# Sheet2.net
KiCad netlist of a schematic drawn in Altium Designer
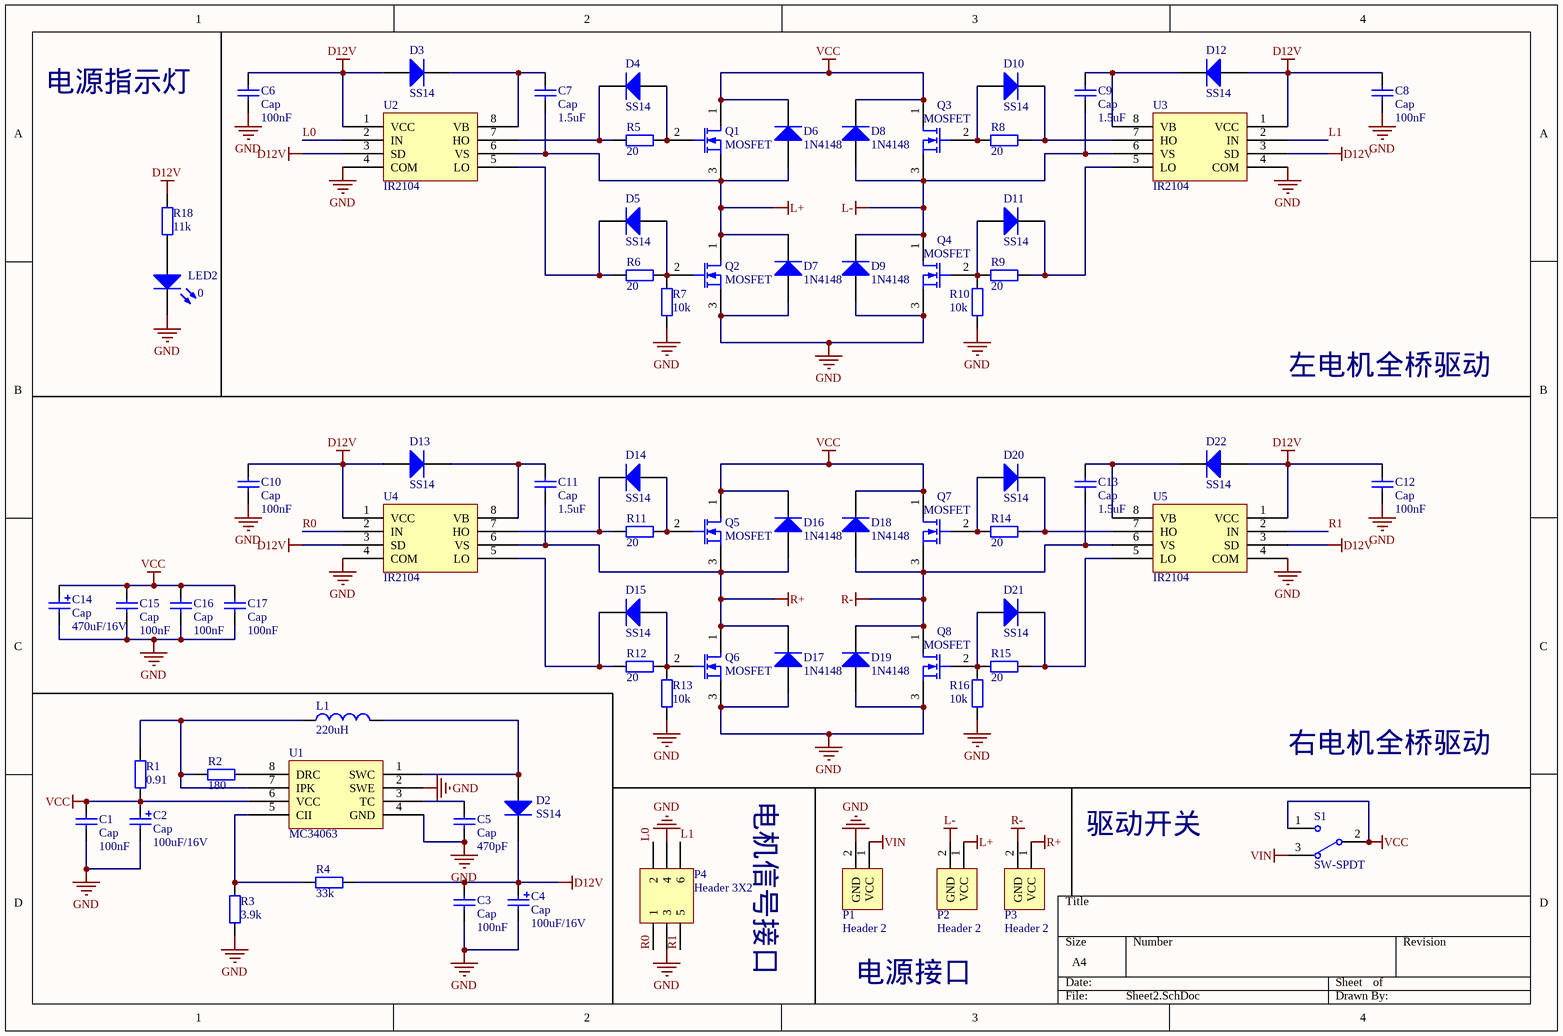
[diagram p0: Sheet2.SchDoc]

(export (version "E")
  (design (tool "Eeschema 10.0.6"))
  (components
    (comp (ref "C1")
      (value "Cap")
      (footprint "0603C")
      (description "Capacitor")
      (fields (field (name "ALTIUM_VALUE") "100nF") (field (name "PUBLISHER") "Altium Limited"))
      (libsource (lib "Schlib1") (part "Cap"))
    )
    (comp (ref "C2")
      (value "Cap")
      (footprint "电解电容")
      (description "Capacitor")
      (fields (field (name "ALTIUM_VALUE") "100uF/16V") (field (name "PUBLISHER") "Altium Limited"))
      (libsource (lib "Schlib1") (part "Cap2"))
    )
    (comp (ref "C3")
      (value "Cap")
      (footprint "0603C")
      (description "Capacitor")
      (fields (field (name "ALTIUM_VALUE") "100nF") (field (name "PUBLISHER") "Altium Limited"))
      (libsource (lib "Schlib1") (part "Cap"))
    )
    (comp (ref "C4")
      (value "Cap")
      (footprint "电解电容")
      (description "Capacitor")
      (fields (field (name "ALTIUM_VALUE") "100uF/16V") (field (name "PUBLISHER") "Altium Limited"))
      (libsource (lib "Schlib1") (part "Cap2"))
    )
    (comp (ref "C5")
      (value "Cap")
      (footprint "0603C")
      (description "Capacitor")
      (fields (field (name "ALTIUM_VALUE") "470pF") (field (name "PUBLISHER") "Altium Limited"))
      (libsource (lib "Schlib1") (part "Cap"))
    )
    (comp (ref "C6")
      (value "Cap")
      (footprint "0603C")
      (description "Capacitor")
      (fields (field (name "ALTIUM_VALUE") "100nF") (field (name "PUBLISHER") "Altium Limited"))
      (libsource (lib "Schlib1") (part "Cap"))
    )
    (comp (ref "C7")
      (value "Cap")
      (footprint "0603C")
      (description "Capacitor")
      (fields (field (name "ALTIUM_VALUE") "1.5uF") (field (name "PUBLISHER") "Altium Limited"))
      (libsource (lib "Schlib1") (part "Cap"))
    )
    (comp (ref "C8")
      (value "Cap")
      (footprint "0603C")
      (description "Capacitor")
      (fields (field (name "ALTIUM_VALUE") "100nF") (field (name "PUBLISHER") "Altium Limited"))
      (libsource (lib "Schlib1") (part "Cap"))
    )
    (comp (ref "C9")
      (value "Cap")
      (footprint "0603C")
      (description "Capacitor")
      (fields (field (name "ALTIUM_VALUE") "1.5uF") (field (name "PUBLISHER") "Altium Limited"))
      (libsource (lib "Schlib1") (part "Cap"))
    )
    (comp (ref "C10")
      (value "Cap")
      (footprint "0603C")
      (description "Capacitor")
      (fields (field (name "ALTIUM_VALUE") "100nF") (field (name "PUBLISHER") "Altium Limited"))
      (libsource (lib "Schlib1") (part "Cap"))
    )
    (comp (ref "C11")
      (value "Cap")
      (footprint "0603C")
      (description "Capacitor")
      (fields (field (name "ALTIUM_VALUE") "1.5uF") (field (name "PUBLISHER") "Altium Limited"))
      (libsource (lib "Schlib1") (part "Cap"))
    )
    (comp (ref "C12")
      (value "Cap")
      (footprint "0603C")
      (description "Capacitor")
      (fields (field (name "ALTIUM_VALUE") "100nF") (field (name "PUBLISHER") "Altium Limited"))
      (libsource (lib "Schlib1") (part "Cap"))
    )
    (comp (ref "C13")
      (value "Cap")
      (footprint "0603C")
      (description "Capacitor")
      (fields (field (name "ALTIUM_VALUE") "1.5uF") (field (name "PUBLISHER") "Altium Limited"))
      (libsource (lib "Schlib1") (part "Cap"))
    )
    (comp (ref "C14")
      (value "Cap")
      (footprint "CAP5.08/8")
      (description "Capacitor")
      (fields (field (name "ALTIUM_VALUE") "470uF/16V") (field (name "PUBLISHER") "Altium Limited"))
      (libsource (lib "Schlib1") (part "Cap2"))
    )
    (comp (ref "C15")
      (value "Cap")
      (footprint "0603C")
      (description "Capacitor")
      (fields (field (name "ALTIUM_VALUE") "100nF") (field (name "PUBLISHER") "Altium Limited"))
      (libsource (lib "Schlib1") (part "Cap"))
    )
    (comp (ref "C16")
      (value "Cap")
      (footprint "0603C")
      (description "Capacitor")
      (fields (field (name "ALTIUM_VALUE") "100nF") (field (name "PUBLISHER") "Altium Limited"))
      (libsource (lib "Schlib1") (part "Cap"))
    )
    (comp (ref "C17")
      (value "Cap")
      (footprint "0603C")
      (description "Capacitor")
      (fields (field (name "ALTIUM_VALUE") "100nF") (field (name "PUBLISHER") "Altium Limited"))
      (libsource (lib "Schlib1") (part "Cap"))
    )
    (comp (ref "D2")
      (value "SS14")
      (footprint "ss54")
      (description "Default Diode")
      (fields (field (name "PUBLISHER") "Altium Limited"))
      (libsource (lib "Schlib1") (part "Diode_1"))
    )
    (comp (ref "D3")
      (value "SS14")
      (footprint "ss54")
      (description "Default Diode")
      (fields (field (name "PUBLISHER") "Altium Limited"))
      (libsource (lib "Schlib1") (part "Diode_1"))
    )
    (comp (ref "D4")
      (value "SS14")
      (footprint "ss54")
      (description "Default Diode")
      (fields (field (name "PUBLISHER") "Altium Limited"))
      (libsource (lib "Schlib1") (part "Diode_1"))
    )
    (comp (ref "D5")
      (value "SS14")
      (footprint "ss54")
      (description "Default Diode")
      (fields (field (name "PUBLISHER") "Altium Limited"))
      (libsource (lib "Schlib1") (part "Diode_1"))
    )
    (comp (ref "D6")
      (value "1N4148")
      (footprint "SOD123")
      (description "Default Diode")
      (fields (field (name "PUBLISHER") "Altium Limited"))
      (libsource (lib "Schlib1") (part "Diode_2"))
    )
    (comp (ref "D7")
      (value "1N4148")
      (footprint "SOD123")
      (description "Default Diode")
      (fields (field (name "PUBLISHER") "Altium Limited"))
      (libsource (lib "Schlib1") (part "Diode_2"))
    )
    (comp (ref "D8")
      (value "1N4148")
      (footprint "SOD123")
      (description "Default Diode")
      (fields (field (name "PUBLISHER") "Altium Limited"))
      (libsource (lib "Schlib1") (part "Diode_2"))
    )
    (comp (ref "D9")
      (value "1N4148")
      (footprint "SOD123")
      (description "Default Diode")
      (fields (field (name "PUBLISHER") "Altium Limited"))
      (libsource (lib "Schlib1") (part "Diode_2"))
    )
    (comp (ref "D10")
      (value "SS14")
      (footprint "ss54")
      (description "Default Diode")
      (fields (field (name "PUBLISHER") "Altium Limited"))
      (libsource (lib "Schlib1") (part "Diode_1"))
    )
    (comp (ref "D11")
      (value "SS14")
      (footprint "ss54")
      (description "Default Diode")
      (fields (field (name "PUBLISHER") "Altium Limited"))
      (libsource (lib "Schlib1") (part "Diode_1"))
    )
    (comp (ref "D12")
      (value "SS14")
      (footprint "ss54")
      (description "Default Diode")
      (fields (field (name "PUBLISHER") "Altium Limited"))
      (libsource (lib "Schlib1") (part "Diode_1"))
    )
    (comp (ref "D13")
      (value "SS14")
      (footprint "ss54")
      (description "Default Diode")
      (fields (field (name "PUBLISHER") "Altium Limited"))
      (libsource (lib "Schlib1") (part "Diode_1"))
    )
    (comp (ref "D14")
      (value "SS14")
      (footprint "ss54")
      (description "Default Diode")
      (fields (field (name "PUBLISHER") "Altium Limited"))
      (libsource (lib "Schlib1") (part "Diode_1"))
    )
    (comp (ref "D15")
      (value "SS14")
      (footprint "ss54")
      (description "Default Diode")
      (fields (field (name "PUBLISHER") "Altium Limited"))
      (libsource (lib "Schlib1") (part "Diode_1"))
    )
    (comp (ref "D16")
      (value "1N4148")
      (footprint "SOD123")
      (description "Default Diode")
      (fields (field (name "PUBLISHER") "Altium Limited"))
      (libsource (lib "Schlib1") (part "Diode_2"))
    )
    (comp (ref "D17")
      (value "1N4148")
      (footprint "SOD123")
      (description "Default Diode")
      (fields (field (name "PUBLISHER") "Altium Limited"))
      (libsource (lib "Schlib1") (part "Diode_2"))
    )
    (comp (ref "D18")
      (value "1N4148")
      (footprint "SOD123")
      (description "Default Diode")
      (fields (field (name "PUBLISHER") "Altium Limited"))
      (libsource (lib "Schlib1") (part "Diode_2"))
    )
    (comp (ref "D19")
      (value "1N4148")
      (footprint "SOD123")
      (description "Default Diode")
      (fields (field (name "PUBLISHER") "Altium Limited"))
      (libsource (lib "Schlib1") (part "Diode_2"))
    )
    (comp (ref "D20")
      (value "SS14")
      (footprint "ss54")
      (description "Default Diode")
      (fields (field (name "PUBLISHER") "Altium Limited"))
      (libsource (lib "Schlib1") (part "Diode_1"))
    )
    (comp (ref "D21")
      (value "SS14")
      (footprint "ss54")
      (description "Default Diode")
      (fields (field (name "PUBLISHER") "Altium Limited"))
      (libsource (lib "Schlib1") (part "Diode_1"))
    )
    (comp (ref "D22")
      (value "SS14")
      (footprint "ss54")
      (description "Default Diode")
      (fields (field (name "PUBLISHER") "Altium Limited"))
      (libsource (lib "Schlib1") (part "Diode_1"))
    )
    (comp (ref "L1")
      (value "220uH")
      (footprint "cd54")
      (description "Inductor")
      (fields (field (name "PUBLISHER") "Altium Limited"))
      (libsource (lib "Schlib1") (part "Inductor_2"))
    )
    (comp (ref "LED2")
      (value "0")
      (footprint "0603C")
      (description "Typical RED, GREEN, YELLOW, AMBER GaAs LED")
      (fields (field (name "PUBLISHER") "Altium Limited"))
      (libsource (lib "Schlib1") (part "LED2"))
    )
    (comp (ref "P1")
      (value "Header 2")
      (footprint "VCCBAT")
      (description "Header, 2-Pin")
      (fields (field (name "PUBLISHER") "Altium Limited"))
      (libsource (lib "Schlib1") (part "Header 2_2"))
    )
    (comp (ref "P2")
      (value "Header 2")
      (footprint "VCCBAT")
      (description "Header, 2-Pin")
      (fields (field (name "PUBLISHER") "Altium Limited"))
      (libsource (lib "Schlib1") (part "Header 2_2"))
    )
    (comp (ref "P3")
      (value "Header 2")
      (footprint "VCCBAT")
      (description "Header, 2-Pin")
      (fields (field (name "PUBLISHER") "Altium Limited"))
      (libsource (lib "Schlib1") (part "Header 2_2"))
    )
    (comp (ref "P4")
      (value "Header 3X2")
      (footprint "HDR2X3")
      (description "Header, 3-Pin, Dual row")
      (fields (field (name "PUBLISHER") "Altium Limited"))
      (libsource (lib "Miscellaneous Connectors") (part "Header 3X2"))
    )
    (comp (ref "Q1") (value "MOSFET") (footprint "DPAK-1") (libsource (lib "Schlib1") (part "MOSFET-N")))
    (comp (ref "Q2") (value "MOSFET") (footprint "DPAK-1") (libsource (lib "Schlib1") (part "MOSFET-N")))
    (comp (ref "Q3") (value "MOSFET") (footprint "DPAK-1") (libsource (lib "Schlib1") (part "MOSFET-N")))
    (comp (ref "Q4") (value "MOSFET") (footprint "DPAK-1") (libsource (lib "Schlib1") (part "MOSFET-N")))
    (comp (ref "Q5") (value "MOSFET") (footprint "DPAK-1") (libsource (lib "Schlib1") (part "MOSFET-N")))
    (comp (ref "Q6") (value "MOSFET") (footprint "DPAK-1") (libsource (lib "Schlib1") (part "MOSFET-N")))
    (comp (ref "Q7") (value "MOSFET") (footprint "DPAK-1") (libsource (lib "Schlib1") (part "MOSFET-N")))
    (comp (ref "Q8") (value "MOSFET") (footprint "DPAK-1") (libsource (lib "Schlib1") (part "MOSFET-N")))
    (comp (ref "R1")
      (value "0.91")
      (footprint "0603R")
      (description "Resistor")
      (fields (field (name "Comment") "Res2") (field (name "PUBLISHER") "Altium Limited"))
      (libsource (lib "Schlib1") (part "Res2"))
    )
    (comp (ref "R2")
      (value "180")
      (footprint "0603R")
      (description "Resistor")
      (fields (field (name "Comment") "Res2") (field (name "PUBLISHER") "Altium Limited"))
      (libsource (lib "") (part "Res2_1"))
    )
    (comp (ref "R3")
      (value "3.9k")
      (footprint "0603R")
      (description "Resistor")
      (fields (field (name "Comment") "Res2") (field (name "PUBLISHER") "Altium Limited"))
      (libsource (lib "") (part "Res2_2"))
    )
    (comp (ref "R4")
      (value "33k")
      (footprint "0603R")
      (description "Resistor")
      (fields (field (name "Comment") "Res2") (field (name "PUBLISHER") "Altium Limited"))
      (libsource (lib "") (part "Res2_1"))
    )
    (comp (ref "R5")
      (value "20")
      (footprint "0603R")
      (description "Resistor")
      (fields (field (name "Comment") "Res2") (field (name "PUBLISHER") "Altium Limited"))
      (libsource (lib "") (part "Res2_1"))
    )
    (comp (ref "R6")
      (value "20")
      (footprint "0603R")
      (description "Resistor")
      (fields (field (name "Comment") "Res2") (field (name "PUBLISHER") "Altium Limited"))
      (libsource (lib "") (part "Res2_1"))
    )
    (comp (ref "R7")
      (value "10k")
      (footprint "0603R")
      (description "Resistor")
      (fields (field (name "Comment") "Res2") (field (name "PUBLISHER") "Altium Limited"))
      (libsource (lib "Schlib1") (part "Res2"))
    )
    (comp (ref "R8")
      (value "20")
      (footprint "0603R")
      (description "Resistor")
      (fields (field (name "Comment") "Res2") (field (name "PUBLISHER") "Altium Limited"))
      (libsource (lib "Schlib1") (part "Res2"))
    )
    (comp (ref "R9")
      (value "20")
      (footprint "0603R")
      (description "Resistor")
      (fields (field (name "Comment") "Res2") (field (name "PUBLISHER") "Altium Limited"))
      (libsource (lib "Schlib1") (part "Res2"))
    )
    (comp (ref "R10")
      (value "10k")
      (footprint "0603R")
      (description "Resistor")
      (fields (field (name "Comment") "Res2") (field (name "PUBLISHER") "Altium Limited"))
      (libsource (lib "") (part "Res2_3"))
    )
    (comp (ref "R11")
      (value "20")
      (footprint "0603R")
      (description "Resistor")
      (fields (field (name "Comment") "Res2") (field (name "PUBLISHER") "Altium Limited"))
      (libsource (lib "") (part "Res2_1"))
    )
    (comp (ref "R12")
      (value "20")
      (footprint "0603R")
      (description "Resistor")
      (fields (field (name "Comment") "Res2") (field (name "PUBLISHER") "Altium Limited"))
      (libsource (lib "") (part "Res2_1"))
    )
    (comp (ref "R13")
      (value "10k")
      (footprint "0603R")
      (description "Resistor")
      (fields (field (name "Comment") "Res2") (field (name "PUBLISHER") "Altium Limited"))
      (libsource (lib "Schlib1") (part "Res2"))
    )
    (comp (ref "R14")
      (value "20")
      (footprint "0603R")
      (description "Resistor")
      (fields (field (name "Comment") "Res2") (field (name "PUBLISHER") "Altium Limited"))
      (libsource (lib "Schlib1") (part "Res2"))
    )
    (comp (ref "R15")
      (value "20")
      (footprint "0603R")
      (description "Resistor")
      (fields (field (name "Comment") "Res2") (field (name "PUBLISHER") "Altium Limited"))
      (libsource (lib "Schlib1") (part "Res2"))
    )
    (comp (ref "R16")
      (value "10k")
      (footprint "0603R")
      (description "Resistor")
      (fields (field (name "Comment") "Res2") (field (name "PUBLISHER") "Altium Limited"))
      (libsource (lib "") (part "Res2_3"))
    )
    (comp (ref "R18")
      (value "11k")
      (footprint "0603R")
      (description "Resistor")
      (fields (field (name "Comment") "Res2") (field (name "PUBLISHER") "Altium Limited"))
      (libsource (lib "Schlib1") (part "Res2"))
    )
    (comp (ref "S1")
      (value "SW-SPDT")
      (footprint "SW")
      (description "SPDT Subminiature Toggle Switch, Right Angle Mounting, Vertical Actuation")
      (fields (field (name "PUBLISHER") "Altium Limited"))
      (libsource (lib "Miscellaneous Devices") (part "SW-SPDT"))
    )
    (comp (ref "U1") (value "MC34063") (footprint "SOIC-8") (libsource (lib "Schlib1") (part "MC34063")))
    (comp (ref "U2") (value "IR2104") (footprint "SOIC-8") (libsource (lib "") (part "IR2104_1")))
    (comp (ref "U3") (value "IR2104") (footprint "SOIC-8") (libsource (lib "Schlib1") (part "IR2104")))
    (comp (ref "U4") (value "IR2104") (footprint "SOIC-8") (libsource (lib "") (part "IR2104_1")))
    (comp (ref "U5") (value "IR2104") (footprint "SOIC-8") (libsource (lib "Schlib1") (part "IR2104")))
  )
  (nets
    (net (code "1") (name "/L0") (class "Default")
      (node (ref "P4") (pin "2") (pinfunction "2_2") (pintype "passive"))
      (node (ref "U2") (pin "2") (pinfunction "IN_2") (pintype "passive"))
    )
    (net (code "2") (name "/L1") (class "Default")
      (node (ref "P4") (pin "6") (pinfunction "6_6") (pintype "passive"))
      (node (ref "U3") (pin "2") (pinfunction "IN_2") (pintype "passive"))
    )
    (net (code "3") (name "/R0") (class "Default")
      (node (ref "P4") (pin "1") (pinfunction "1_1") (pintype "passive"))
      (node (ref "U4") (pin "2") (pinfunction "IN_2") (pintype "passive"))
    )
    (net (code "4") (name "/R1") (class "Default")
      (node (ref "P4") (pin "5") (pinfunction "5_5") (pintype "passive"))
      (node (ref "U5") (pin "2") (pinfunction "IN_2") (pintype "passive"))
    )
    (net (code "5") (name "D12V") (class "Default")
      (node (ref "C10") (pin "2") (pinfunction "2_2") (pintype "passive"))
      (node (ref "C12") (pin "2") (pinfunction "2_2") (pintype "passive"))
      (node (ref "C3") (pin "2") (pinfunction "2_2") (pintype "passive"))
      (node (ref "C4") (pin "1") (pinfunction "1_1") (pintype "passive"))
      (node (ref "C6") (pin "2") (pinfunction "2_2") (pintype "passive"))
      (node (ref "C8") (pin "2") (pinfunction "2_2") (pintype "passive"))
      (node (ref "D12") (pin "1") (pinfunction "A_1") (pintype "passive"))
      (node (ref "D13") (pin "1") (pinfunction "A_1") (pintype "passive"))
      (node (ref "D2") (pin "2") (pinfunction "K_2") (pintype "passive"))
      (node (ref "D22") (pin "1") (pinfunction "A_1") (pintype "passive"))
      (node (ref "D3") (pin "1") (pinfunction "A_1") (pintype "passive"))
      (node (ref "R18") (pin "2") (pinfunction "2_2") (pintype "passive"))
      (node (ref "R4") (pin "1") (pinfunction "1_1") (pintype "passive"))
      (node (ref "U2") (pin "1") (pinfunction "VCC_1") (pintype "passive"))
      (node (ref "U2") (pin "3") (pinfunction "SD_3") (pintype "passive"))
      (node (ref "U3") (pin "1") (pinfunction "VCC_1") (pintype "passive"))
      (node (ref "U3") (pin "3") (pinfunction "SD_3") (pintype "passive"))
      (node (ref "U4") (pin "1") (pinfunction "VCC_1") (pintype "passive"))
      (node (ref "U4") (pin "3") (pinfunction "SD_3") (pintype "passive"))
      (node (ref "U5") (pin "1") (pinfunction "VCC_1") (pintype "passive"))
      (node (ref "U5") (pin "3") (pinfunction "SD_3") (pintype "passive"))
    )
    (net (code "6") (name "GND") (class "Default")
      (node (ref "C1") (pin "1") (pinfunction "1_1") (pintype "passive"))
      (node (ref "C10") (pin "1") (pinfunction "1_1") (pintype "passive"))
      (node (ref "C12") (pin "1") (pinfunction "1_1") (pintype "passive"))
      (node (ref "C14") (pin "2") (pinfunction "2_2") (pintype "passive"))
      (node (ref "C15") (pin "1") (pinfunction "1_1") (pintype "passive"))
      (node (ref "C16") (pin "1") (pinfunction "1_1") (pintype "passive"))
      (node (ref "C17") (pin "1") (pinfunction "1_1") (pintype "passive"))
      (node (ref "C2") (pin "2") (pinfunction "2_2") (pintype "passive"))
      (node (ref "C3") (pin "1") (pinfunction "1_1") (pintype "passive"))
      (node (ref "C4") (pin "2") (pinfunction "2_2") (pintype "passive"))
      (node (ref "C5") (pin "1") (pinfunction "1_1") (pintype "passive"))
      (node (ref "C6") (pin "1") (pinfunction "1_1") (pintype "passive"))
      (node (ref "C8") (pin "1") (pinfunction "1_1") (pintype "passive"))
      (node (ref "D17") (pin "1") (pinfunction "A_1") (pintype "passive"))
      (node (ref "D19") (pin "1") (pinfunction "A_1") (pintype "passive"))
      (node (ref "D7") (pin "1") (pinfunction "A_1") (pintype "passive"))
      (node (ref "D9") (pin "1") (pinfunction "A_1") (pintype "passive"))
      (node (ref "LED2") (pin "2") (pinfunction "K_2") (pintype "passive"))
      (node (ref "P1") (pin "2") (pinfunction "GND_2") (pintype "passive"))
      (node (ref "P4") (pin "3") (pinfunction "3_3") (pintype "passive"))
      (node (ref "P4") (pin "4") (pinfunction "4_4") (pintype "passive"))
      (node (ref "Q2") (pin "3") (pinfunction "3_3") (pintype "passive"))
      (node (ref "Q4") (pin "3") (pinfunction "3_3") (pintype "passive"))
      (node (ref "Q6") (pin "3") (pinfunction "3_3") (pintype "passive"))
      (node (ref "Q8") (pin "3") (pinfunction "3_3") (pintype "passive"))
      (node (ref "R10") (pin "1") (pinfunction "1_1") (pintype "passive"))
      (node (ref "R13") (pin "1") (pinfunction "1_1") (pintype "passive"))
      (node (ref "R16") (pin "1") (pinfunction "1_1") (pintype "passive"))
      (node (ref "R3") (pin "2") (pinfunction "2_2") (pintype "passive"))
      (node (ref "R7") (pin "1") (pinfunction "1_1") (pintype "passive"))
      (node (ref "U1") (pin "2") (pinfunction "SWE_2") (pintype "passive"))
      (node (ref "U1") (pin "4") (pinfunction "GND_4") (pintype "passive"))
      (node (ref "U2") (pin "4") (pinfunction "COM_4") (pintype "passive"))
      (node (ref "U3") (pin "4") (pinfunction "COM_4") (pintype "passive"))
      (node (ref "U4") (pin "4") (pinfunction "COM_4") (pintype "passive"))
      (node (ref "U5") (pin "4") (pinfunction "COM_4") (pintype "passive"))
    )
    (net (code "7") (name "L+") (class "Default")
      (node (ref "C7") (pin "1") (pinfunction "1_1") (pintype "passive"))
      (node (ref "D6") (pin "1") (pinfunction "A_1") (pintype "passive"))
      (node (ref "D7") (pin "2") (pinfunction "K_2") (pintype "passive"))
      (node (ref "P2") (pin "1") (pinfunction "VCC_1") (pintype "passive"))
      (node (ref "Q1") (pin "3") (pinfunction "3_3") (pintype "passive"))
      (node (ref "Q2") (pin "1") (pinfunction "D_1") (pintype "passive"))
      (node (ref "U2") (pin "6") (pinfunction "VS_6") (pintype "passive"))
    )
    (net (code "8") (name "L-") (class "Default")
      (node (ref "C9") (pin "1") (pinfunction "1_1") (pintype "passive"))
      (node (ref "D8") (pin "1") (pinfunction "A_1") (pintype "passive"))
      (node (ref "D9") (pin "2") (pinfunction "K_2") (pintype "passive"))
      (node (ref "P2") (pin "2") (pinfunction "GND_2") (pintype "passive"))
      (node (ref "Q3") (pin "3") (pinfunction "3_3") (pintype "passive"))
      (node (ref "Q4") (pin "1") (pinfunction "D_1") (pintype "passive"))
      (node (ref "U3") (pin "6") (pinfunction "VS_6") (pintype "passive"))
    )
    (net (code "9") (name "Net-(D2-A)") (class "Default")
      (node (ref "D2") (pin "1") (pinfunction "A_1") (pintype "passive"))
      (node (ref "L1") (pin "2") (pinfunction "2_2") (pintype "passive"))
      (node (ref "U1") (pin "1") (pinfunction "SWC_1") (pintype "passive"))
    )
    (net (code "10") (name "Net-(D3-K)") (class "Default")
      (node (ref "C7") (pin "2") (pinfunction "2_2") (pintype "passive"))
      (node (ref "D3") (pin "2") (pinfunction "K_2") (pintype "passive"))
      (node (ref "U2") (pin "8") (pinfunction "VB_8") (pintype "passive"))
    )
    (net (code "11") (name "Net-(D4-A)") (class "Default")
      (node (ref "D4") (pin "1") (pinfunction "A_1") (pintype "passive"))
      (node (ref "Q1") (pin "2") (pinfunction "G_2") (pintype "passive"))
      (node (ref "R5") (pin "1") (pinfunction "1_1") (pintype "passive"))
    )
    (net (code "12") (name "Net-(D4-K)") (class "Default")
      (node (ref "D4") (pin "2") (pinfunction "K_2") (pintype "passive"))
      (node (ref "R5") (pin "2") (pinfunction "2_2") (pintype "passive"))
      (node (ref "U2") (pin "7") (pinfunction "HO_7") (pintype "passive"))
    )
    (net (code "13") (name "Net-(D5-A)") (class "Default")
      (node (ref "D5") (pin "1") (pinfunction "A_1") (pintype "passive"))
      (node (ref "Q2") (pin "2") (pinfunction "G_2") (pintype "passive"))
      (node (ref "R6") (pin "1") (pinfunction "1_1") (pintype "passive"))
      (node (ref "R7") (pin "2") (pinfunction "2_2") (pintype "passive"))
    )
    (net (code "14") (name "Net-(D5-K)") (class "Default")
      (node (ref "D5") (pin "2") (pinfunction "K_2") (pintype "passive"))
      (node (ref "R6") (pin "2") (pinfunction "2_2") (pintype "passive"))
      (node (ref "U2") (pin "5") (pinfunction "LO_5") (pintype "passive"))
    )
    (net (code "15") (name "Net-(D10-A)") (class "Default")
      (node (ref "D10") (pin "1") (pinfunction "A_1") (pintype "passive"))
      (node (ref "Q3") (pin "2") (pinfunction "G_2") (pintype "passive"))
      (node (ref "R8") (pin "1") (pinfunction "1_1") (pintype "passive"))
    )
    (net (code "16") (name "Net-(D10-K)") (class "Default")
      (node (ref "D10") (pin "2") (pinfunction "K_2") (pintype "passive"))
      (node (ref "R8") (pin "2") (pinfunction "2_2") (pintype "passive"))
      (node (ref "U3") (pin "7") (pinfunction "HO_7") (pintype "passive"))
    )
    (net (code "17") (name "Net-(D11-A)") (class "Default")
      (node (ref "D11") (pin "1") (pinfunction "A_1") (pintype "passive"))
      (node (ref "Q4") (pin "2") (pinfunction "G_2") (pintype "passive"))
      (node (ref "R10") (pin "2") (pinfunction "2_2") (pintype "passive"))
      (node (ref "R9") (pin "1") (pinfunction "1_1") (pintype "passive"))
    )
    (net (code "18") (name "Net-(D11-K)") (class "Default")
      (node (ref "D11") (pin "2") (pinfunction "K_2") (pintype "passive"))
      (node (ref "R9") (pin "2") (pinfunction "2_2") (pintype "passive"))
      (node (ref "U3") (pin "5") (pinfunction "LO_5") (pintype "passive"))
    )
    (net (code "19") (name "Net-(D12-K)") (class "Default")
      (node (ref "C9") (pin "2") (pinfunction "2_2") (pintype "passive"))
      (node (ref "D12") (pin "2") (pinfunction "K_2") (pintype "passive"))
      (node (ref "U3") (pin "8") (pinfunction "VB_8") (pintype "passive"))
    )
    (net (code "20") (name "Net-(D13-K)") (class "Default")
      (node (ref "C11") (pin "2") (pinfunction "2_2") (pintype "passive"))
      (node (ref "D13") (pin "2") (pinfunction "K_2") (pintype "passive"))
      (node (ref "U4") (pin "8") (pinfunction "VB_8") (pintype "passive"))
    )
    (net (code "21") (name "Net-(D14-A)") (class "Default")
      (node (ref "D14") (pin "1") (pinfunction "A_1") (pintype "passive"))
      (node (ref "Q5") (pin "2") (pinfunction "G_2") (pintype "passive"))
      (node (ref "R11") (pin "1") (pinfunction "1_1") (pintype "passive"))
    )
    (net (code "22") (name "Net-(D14-K)") (class "Default")
      (node (ref "D14") (pin "2") (pinfunction "K_2") (pintype "passive"))
      (node (ref "R11") (pin "2") (pinfunction "2_2") (pintype "passive"))
      (node (ref "U4") (pin "7") (pinfunction "HO_7") (pintype "passive"))
    )
    (net (code "23") (name "Net-(D15-A)") (class "Default")
      (node (ref "D15") (pin "1") (pinfunction "A_1") (pintype "passive"))
      (node (ref "Q6") (pin "2") (pinfunction "G_2") (pintype "passive"))
      (node (ref "R12") (pin "1") (pinfunction "1_1") (pintype "passive"))
      (node (ref "R13") (pin "2") (pinfunction "2_2") (pintype "passive"))
    )
    (net (code "24") (name "Net-(D15-K)") (class "Default")
      (node (ref "D15") (pin "2") (pinfunction "K_2") (pintype "passive"))
      (node (ref "R12") (pin "2") (pinfunction "2_2") (pintype "passive"))
      (node (ref "U4") (pin "5") (pinfunction "LO_5") (pintype "passive"))
    )
    (net (code "25") (name "Net-(D20-A)") (class "Default")
      (node (ref "D20") (pin "1") (pinfunction "A_1") (pintype "passive"))
      (node (ref "Q7") (pin "2") (pinfunction "G_2") (pintype "passive"))
      (node (ref "R14") (pin "1") (pinfunction "1_1") (pintype "passive"))
    )
    (net (code "26") (name "Net-(D20-K)") (class "Default")
      (node (ref "D20") (pin "2") (pinfunction "K_2") (pintype "passive"))
      (node (ref "R14") (pin "2") (pinfunction "2_2") (pintype "passive"))
      (node (ref "U5") (pin "7") (pinfunction "HO_7") (pintype "passive"))
    )
    (net (code "27") (name "Net-(D21-A)") (class "Default")
      (node (ref "D21") (pin "1") (pinfunction "A_1") (pintype "passive"))
      (node (ref "Q8") (pin "2") (pinfunction "G_2") (pintype "passive"))
      (node (ref "R15") (pin "1") (pinfunction "1_1") (pintype "passive"))
      (node (ref "R16") (pin "2") (pinfunction "2_2") (pintype "passive"))
    )
    (net (code "28") (name "Net-(D21-K)") (class "Default")
      (node (ref "D21") (pin "2") (pinfunction "K_2") (pintype "passive"))
      (node (ref "R15") (pin "2") (pinfunction "2_2") (pintype "passive"))
      (node (ref "U5") (pin "5") (pinfunction "LO_5") (pintype "passive"))
    )
    (net (code "29") (name "Net-(D22-K)") (class "Default")
      (node (ref "C13") (pin "2") (pinfunction "2_2") (pintype "passive"))
      (node (ref "D22") (pin "2") (pinfunction "K_2") (pintype "passive"))
      (node (ref "U5") (pin "8") (pinfunction "VB_8") (pintype "passive"))
    )
    (net (code "30") (name "Net-(LED2-A)") (class "Default")
      (node (ref "LED2") (pin "1") (pinfunction "A_1") (pintype "passive"))
      (node (ref "R18") (pin "1") (pinfunction "1_1") (pintype "passive"))
    )
    (net (code "31") (name "Net-(U1-CII)") (class "Default")
      (node (ref "R3") (pin "1") (pinfunction "1_1") (pintype "passive"))
      (node (ref "R4") (pin "2") (pinfunction "2_2") (pintype "passive"))
      (node (ref "U1") (pin "5") (pinfunction "CII_5") (pintype "passive"))
    )
    (net (code "32") (name "Net-(U1-DRC)") (class "Default")
      (node (ref "R2") (pin "1") (pinfunction "1_1") (pintype "passive"))
      (node (ref "U1") (pin "8") (pinfunction "DRC_8") (pintype "passive"))
    )
    (net (code "33") (name "Net-(U1-IPK)") (class "Default")
      (node (ref "L1") (pin "1") (pinfunction "1_1") (pintype "passive"))
      (node (ref "R1") (pin "2") (pinfunction "2_2") (pintype "passive"))
      (node (ref "R2") (pin "2") (pinfunction "2_2") (pintype "passive"))
      (node (ref "U1") (pin "7") (pinfunction "IPK_7") (pintype "passive"))
    )
    (net (code "34") (name "Net-(U1-TC)") (class "Default")
      (node (ref "C5") (pin "2") (pinfunction "2_2") (pintype "passive"))
      (node (ref "U1") (pin "3") (pinfunction "TC_3") (pintype "passive"))
    )
    (net (code "35") (name "R+") (class "Default")
      (node (ref "C11") (pin "1") (pinfunction "1_1") (pintype "passive"))
      (node (ref "D16") (pin "1") (pinfunction "A_1") (pintype "passive"))
      (node (ref "D17") (pin "2") (pinfunction "K_2") (pintype "passive"))
      (node (ref "P3") (pin "1") (pinfunction "VCC_1") (pintype "passive"))
      (node (ref "Q5") (pin "3") (pinfunction "3_3") (pintype "passive"))
      (node (ref "Q6") (pin "1") (pinfunction "D_1") (pintype "passive"))
      (node (ref "U4") (pin "6") (pinfunction "VS_6") (pintype "passive"))
    )
    (net (code "36") (name "R-") (class "Default")
      (node (ref "C13") (pin "1") (pinfunction "1_1") (pintype "passive"))
      (node (ref "D18") (pin "1") (pinfunction "A_1") (pintype "passive"))
      (node (ref "D19") (pin "2") (pinfunction "K_2") (pintype "passive"))
      (node (ref "P3") (pin "2") (pinfunction "GND_2") (pintype "passive"))
      (node (ref "Q7") (pin "3") (pinfunction "3_3") (pintype "passive"))
      (node (ref "Q8") (pin "1") (pinfunction "D_1") (pintype "passive"))
      (node (ref "U5") (pin "6") (pinfunction "VS_6") (pintype "passive"))
    )
    (net (code "37") (name "VCC") (class "Default")
      (node (ref "C1") (pin "2") (pinfunction "2_2") (pintype "passive"))
      (node (ref "C14") (pin "1") (pinfunction "1_1") (pintype "passive"))
      (node (ref "C15") (pin "2") (pinfunction "2_2") (pintype "passive"))
      (node (ref "C16") (pin "2") (pinfunction "2_2") (pintype "passive"))
      (node (ref "C17") (pin "2") (pinfunction "2_2") (pintype "passive"))
      (node (ref "C2") (pin "1") (pinfunction "1_1") (pintype "passive"))
      (node (ref "D16") (pin "2") (pinfunction "K_2") (pintype "passive"))
      (node (ref "D18") (pin "2") (pinfunction "K_2") (pintype "passive"))
      (node (ref "D6") (pin "2") (pinfunction "K_2") (pintype "passive"))
      (node (ref "D8") (pin "2") (pinfunction "K_2") (pintype "passive"))
      (node (ref "Q1") (pin "1") (pinfunction "D_1") (pintype "passive"))
      (node (ref "Q3") (pin "1") (pinfunction "D_1") (pintype "passive"))
      (node (ref "Q5") (pin "1") (pinfunction "D_1") (pintype "passive"))
      (node (ref "Q7") (pin "1") (pinfunction "D_1") (pintype "passive"))
      (node (ref "R1") (pin "1") (pinfunction "1_1") (pintype "passive"))
      (node (ref "S1") (pin "1") (pinfunction "1_1") (pintype "passive"))
      (node (ref "S1") (pin "2") (pinfunction "2_2") (pintype "passive"))
      (node (ref "U1") (pin "6") (pinfunction "VCC_6") (pintype "passive"))
    )
    (net (code "38") (name "VIN") (class "Default")
      (node (ref "P1") (pin "1") (pinfunction "VCC_1") (pintype "passive"))
      (node (ref "S1") (pin "3") (pinfunction "3_3") (pintype "passive"))
    )
  )
)
